# pcb_schematic.net
KiCad netlist of a schematic drawn in EAGLE
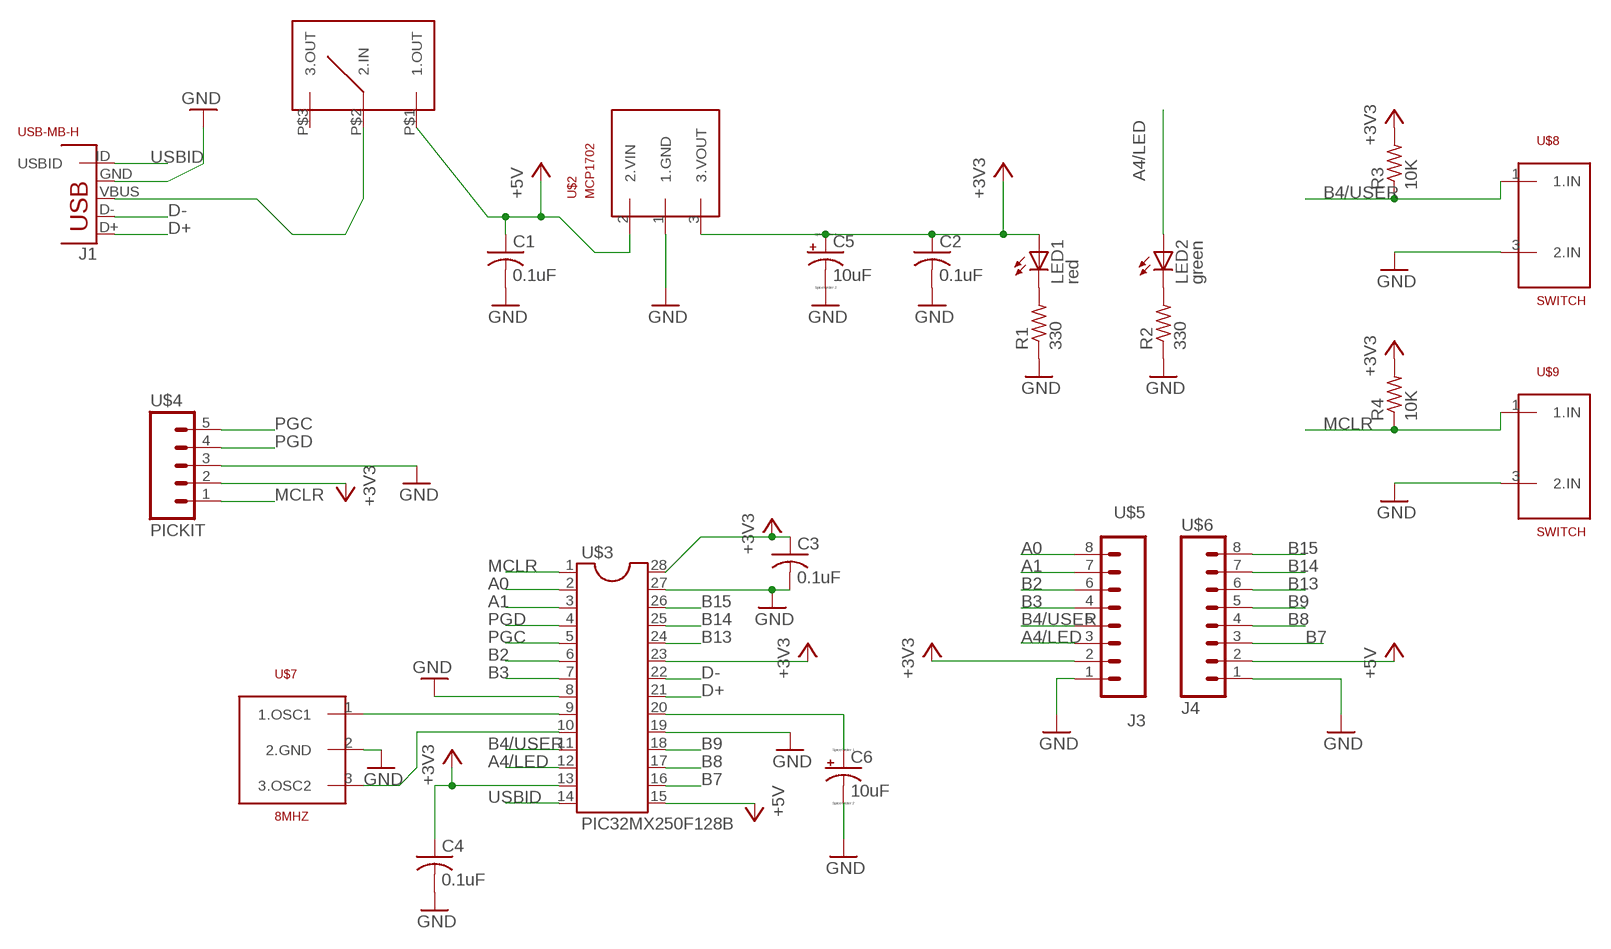
[diagram p0: schematic, sheet 1]

(export (version "E")
  (design (tool "Eeschema 10.0.6"))
  (components
    (comp (ref "C1")
      (value "0.1uF")
      (footprint "eagle-import:C025-025X050")
      (libsource (lib "eagle-import") (part "C-US025-025X050"))
    )
    (comp (ref "C2")
      (value "0.1uF")
      (footprint "eagle-import:C025-025X050")
      (libsource (lib "eagle-import") (part "C-US025-025X050"))
    )
    (comp (ref "C3")
      (value "0.1uF")
      (footprint "eagle-import:C025-025X050")
      (libsource (lib "eagle-import") (part "C-US025-025X050"))
    )
    (comp (ref "C4")
      (value "0.1uF")
      (footprint "eagle-import:C025-025X050")
      (libsource (lib "eagle-import") (part "C-US025-025X050"))
    )
    (comp (ref "C5")
      (value "10uF")
      (footprint "eagle-import:B45181A")
      (libsource (lib "eagle-import") (part "CPOL-USB45181A"))
    )
    (comp (ref "C6")
      (value "10uF")
      (footprint "eagle-import:B45181A")
      (libsource (lib "eagle-import") (part "CPOL-USB45181A"))
    )
    (comp (ref "J1")
      (value "USB-MB-H")
      (footprint "eagle-import:USB-MB-H")
      (libsource (lib "eagle-import") (part "USB-MB-H"))
    )
    (comp (ref "LED1")
      (value "red")
      (footprint "eagle-import:LED3MM")
      (libsource (lib "eagle-import") (part "LED3MM"))
    )
    (comp (ref "LED2")
      (value "green")
      (footprint "eagle-import:LED3MM")
      (libsource (lib "eagle-import") (part "LED3MM"))
    )
    (comp (ref "R1")
      (value "330")
      (footprint "eagle-import:0204_7")
      (libsource (lib "eagle-import") (part "R-US_0204/7"))
    )
    (comp (ref "R2")
      (value "330")
      (footprint "eagle-import:0204_7")
      (libsource (lib "eagle-import") (part "R-US_0204/7"))
    )
    (comp (ref "R3")
      (value "10K")
      (footprint "eagle-import:0204_7")
      (libsource (lib "eagle-import") (part "R-US_0204/7"))
    )
    (comp (ref "R4")
      (value "10K")
      (footprint "eagle-import:0204_7")
      (libsource (lib "eagle-import") (part "R-US_0204/7"))
    )
    (comp (ref "U$1")
      (value "SLIDE_SWITCH")
      (footprint "eagle-import:SLIDE_SWITCH")
      (libsource (lib "eagle-import") (part "SLIDE_SWITCH"))
    )
    (comp (ref "U$2")
      (value "MCP1702")
      (footprint "eagle-import:TO92")
      (libsource (lib "eagle-import") (part "MCP1702"))
    )
    (comp (ref "U$3")
      (value "PIC32MX250F128B")
      (footprint "eagle-import:PIC32MX250F128B")
      (libsource (lib "eagle-import") (part "PIC32MX250F128B"))
    )
    (comp (ref "U$4")
      (value "PICKIT")
      (footprint "eagle-import:PICKIT")
      (libsource (lib "eagle-import") (part "PICKIT"))
    )
    (comp (ref "U$5") (value "J3") (footprint "eagle-import:J3") (libsource (lib "eagle-import") (part "J3")))
    (comp (ref "U$6") (value "J4") (footprint "eagle-import:J4") (libsource (lib "eagle-import") (part "J4")))
    (comp (ref "U$7")
      (value "8MHZ")
      (footprint "eagle-import:8MHZ")
      (libsource (lib "eagle-import") (part "8MHZ"))
    )
    (comp (ref "U$8")
      (value "SWITCH")
      (footprint "eagle-import:SWITCH")
      (libsource (lib "eagle-import") (part "SWITCH"))
    )
    (comp (ref "U$9")
      (value "SWITCH")
      (footprint "eagle-import:SWITCH")
      (libsource (lib "eagle-import") (part "SWITCH"))
    )
  )
  (nets
    (net (code "1") (name "+3V3") (class "Default")
      (node (ref "C2") (pin "1") (pinfunction "1_1") (pintype "passive"))
      (node (ref "C3") (pin "1") (pinfunction "1_1") (pintype "passive"))
      (node (ref "C4") (pin "1") (pinfunction "1_1") (pintype "passive"))
      (node (ref "C5") (pin "+") (pinfunction "+_+") (pintype "passive"))
      (node (ref "LED1") (pin "A") (pinfunction "A_A") (pintype "passive"))
      (node (ref "R3") (pin "2") (pinfunction "2_2") (pintype "passive"))
      (node (ref "R4") (pin "2") (pinfunction "2_2") (pintype "passive"))
      (node (ref "U$2") (pin "3") (pinfunction "3.VOUT_3") (pintype "bidirectional"))
      (node (ref "U$3") (pin "13") (pinfunction "13.VDD_13") (pintype "passive"))
      (node (ref "U$3") (pin "23") (pinfunction "23.VUSB3V3_23") (pintype "passive"))
      (node (ref "U$3") (pin "28") (pinfunction "28.AVDD_28") (pintype "passive"))
      (node (ref "U$4") (pin "2") (pinfunction "2.3V3_2") (pintype "passive"))
      (node (ref "U$5") (pin "2") (pinfunction "2.3V3_2") (pintype "passive"))
    )
    (net (code "2") (name "+5V") (class "Default")
      (node (ref "C1") (pin "1") (pinfunction "1_1") (pintype "passive"))
      (node (ref "U$1") (pin "P$1") (pinfunction "1.OUT_P$1") (pintype "bidirectional"))
      (node (ref "U$2") (pin "2") (pinfunction "2.VIN_2") (pintype "bidirectional"))
      (node (ref "U$3") (pin "15") (pinfunction "15.VBUS_15") (pintype "passive"))
      (node (ref "U$6") (pin "2") (pinfunction "2.5V_2") (pintype "passive"))
    )
    (net (code "3") (name "/A0") (class "Default")
      (node (ref "U$3") (pin "2") (pinfunction "2.A0_2") (pintype "passive"))
      (node (ref "U$5") (pin "8") (pinfunction "8.A0_8") (pintype "passive"))
    )
    (net (code "4") (name "/A1") (class "Default")
      (node (ref "U$3") (pin "3") (pinfunction "3.A1_3") (pintype "passive"))
      (node (ref "U$5") (pin "7") (pinfunction "7.A1_7") (pintype "passive"))
    )
    (net (code "5") (name "/A4{slash}LED") (class "Default")
      (node (ref "LED2") (pin "A") (pinfunction "A_A") (pintype "passive"))
      (node (ref "U$3") (pin "12") (pinfunction "12.A4/LED_12") (pintype "passive"))
      (node (ref "U$5") (pin "3") (pinfunction "3.A4/LED_3") (pintype "passive"))
    )
    (net (code "6") (name "/B2") (class "Default")
      (node (ref "U$3") (pin "6") (pinfunction "6.B2_6") (pintype "passive"))
      (node (ref "U$5") (pin "6") (pinfunction "5.B3_6") (pintype "passive"))
    )
    (net (code "7") (name "/B3") (class "Default")
      (node (ref "U$3") (pin "7") (pinfunction "7.B3_7") (pintype "passive"))
      (node (ref "U$5") (pin "4") (pinfunction "4.B4/USER_4") (pintype "passive"))
    )
    (net (code "8") (name "/B4{slash}USER") (class "Default")
      (node (ref "R3") (pin "1") (pinfunction "1_1") (pintype "passive"))
      (node (ref "U$3") (pin "11") (pinfunction "11.B4/USER_11") (pintype "passive"))
      (node (ref "U$5") (pin "5") (pinfunction "5_5") (pintype "passive"))
      (node (ref "U$8") (pin "1") (pinfunction "1.IN_1") (pintype "bidirectional"))
    )
    (net (code "9") (name "/B7") (class "Default")
      (node (ref "U$3") (pin "16") (pinfunction "16.B7_16") (pintype "passive"))
      (node (ref "U$6") (pin "3") (pinfunction "3.B7_3") (pintype "passive"))
    )
    (net (code "10") (name "/B8") (class "Default")
      (node (ref "U$3") (pin "17") (pinfunction "17.B8_17") (pintype "passive"))
      (node (ref "U$6") (pin "4") (pinfunction "4.B8_4") (pintype "passive"))
    )
    (net (code "11") (name "/B9") (class "Default")
      (node (ref "U$3") (pin "18") (pinfunction "18.B9_18") (pintype "passive"))
      (node (ref "U$6") (pin "5") (pinfunction "5.B9_5") (pintype "passive"))
    )
    (net (code "12") (name "/B13") (class "Default")
      (node (ref "U$3") (pin "24") (pinfunction "24.B13_24") (pintype "passive"))
      (node (ref "U$6") (pin "6") (pinfunction "6.B13_6") (pintype "passive"))
    )
    (net (code "13") (name "/B14") (class "Default")
      (node (ref "U$3") (pin "25") (pinfunction "25.B14_25") (pintype "passive"))
      (node (ref "U$6") (pin "7") (pinfunction "7.B14_7") (pintype "passive"))
    )
    (net (code "14") (name "/B15") (class "Default")
      (node (ref "U$3") (pin "26") (pinfunction "26.B15_26") (pintype "passive"))
      (node (ref "U$6") (pin "8") (pinfunction "8.B15_8") (pintype "passive"))
    )
    (net (code "15") (name "/D+") (class "Default")
      (node (ref "J1") (pin "D+") (pinfunction "D+_D+") (pintype "bidirectional"))
      (node (ref "U$3") (pin "21") (pinfunction "21.D+/B10_21") (pintype "passive"))
    )
    (net (code "16") (name "/D-") (class "Default")
      (node (ref "J1") (pin "D-") (pinfunction "D-_D-") (pintype "bidirectional"))
      (node (ref "U$3") (pin "22") (pinfunction "22.D-/B11_22") (pintype "passive"))
    )
    (net (code "17") (name "/MCLR") (class "Default")
      (node (ref "R4") (pin "1") (pinfunction "1_1") (pintype "passive"))
      (node (ref "U$3") (pin "1") (pinfunction "1.MCLR_1") (pintype "passive"))
      (node (ref "U$4") (pin "1") (pinfunction "1.MCLR_1") (pintype "passive"))
      (node (ref "U$9") (pin "1") (pinfunction "1.IN_1") (pintype "bidirectional"))
    )
    (net (code "18") (name "/PGC") (class "Default")
      (node (ref "U$3") (pin "5") (pinfunction "5.PGC_5") (pintype "passive"))
      (node (ref "U$4") (pin "5") (pinfunction "5.PGC_5") (pintype "passive"))
    )
    (net (code "19") (name "/PGD") (class "Default")
      (node (ref "U$3") (pin "4") (pinfunction "4.PGD_4") (pintype "passive"))
      (node (ref "U$4") (pin "4") (pinfunction "4.PGD_4") (pintype "passive"))
    )
    (net (code "20") (name "/USBID") (class "Default")
      (node (ref "J1") (pin "ID") (pinfunction "USBID_ID") (pintype "bidirectional"))
      (node (ref "U$3") (pin "14") (pinfunction "14.USBID/B5_14") (pintype "passive"))
    )
    (net (code "21") (name "GND") (class "Default")
      (node (ref "C1") (pin "2") (pinfunction "2_2") (pintype "passive"))
      (node (ref "C2") (pin "2") (pinfunction "2_2") (pintype "passive"))
      (node (ref "C3") (pin "2") (pinfunction "2_2") (pintype "passive"))
      (node (ref "C4") (pin "2") (pinfunction "2_2") (pintype "passive"))
      (node (ref "C5") (pin "-") (pinfunction "-_-") (pintype "passive"))
      (node (ref "C6") (pin "-") (pinfunction "-_-") (pintype "passive"))
      (node (ref "J1") (pin "GND") (pinfunction "GND_GND") (pintype "bidirectional"))
      (node (ref "R1") (pin "1") (pinfunction "1_1") (pintype "passive"))
      (node (ref "R2") (pin "1") (pinfunction "1_1") (pintype "passive"))
      (node (ref "U$2") (pin "1") (pinfunction "1.GND_1") (pintype "bidirectional"))
      (node (ref "U$3") (pin "19") (pinfunction "19.VSS_19") (pintype "passive"))
      (node (ref "U$3") (pin "27") (pinfunction "27.AVSS_27") (pintype "passive"))
      (node (ref "U$3") (pin "8") (pinfunction "8.GND_8") (pintype "passive"))
      (node (ref "U$4") (pin "3") (pinfunction "3.GND_3") (pintype "passive"))
      (node (ref "U$5") (pin "1") (pinfunction "1.GND_1") (pintype "passive"))
      (node (ref "U$6") (pin "1") (pinfunction "1.GND_1") (pintype "passive"))
      (node (ref "U$7") (pin "2") (pinfunction "2.GND_2") (pintype "bidirectional"))
      (node (ref "U$8") (pin "3") (pinfunction "2.IN_3") (pintype "bidirectional"))
      (node (ref "U$9") (pin "3") (pinfunction "2.IN_3") (pintype "bidirectional"))
    )
    (net (code "22") (name "Net-(LED1-C)") (class "Default")
      (node (ref "LED1") (pin "K") (pinfunction "C_K") (pintype "passive"))
      (node (ref "R1") (pin "2") (pinfunction "2_2") (pintype "passive"))
    )
    (net (code "23") (name "Net-(LED2-C)") (class "Default")
      (node (ref "LED2") (pin "K") (pinfunction "C_K") (pintype "passive"))
      (node (ref "R2") (pin "2") (pinfunction "2_2") (pintype "passive"))
    )
    (net (code "24") (name "Net-(U$1-2.IN)") (class "Default")
      (node (ref "J1") (pin "VBUS") (pinfunction "VBUS_VBUS") (pintype "bidirectional"))
      (node (ref "U$1") (pin "P$2") (pinfunction "2.IN_P$2") (pintype "bidirectional"))
    )
    (net (code "25") (name "Net-(U$3-9.OSC1)") (class "Default")
      (node (ref "U$3") (pin "9") (pinfunction "9.OSC1_9") (pintype "passive"))
      (node (ref "U$7") (pin "1") (pinfunction "1.OSC1_1") (pintype "bidirectional"))
    )
    (net (code "26") (name "Net-(U$3-10.OSC2)") (class "Default")
      (node (ref "U$3") (pin "10") (pinfunction "10.OSC2_10") (pintype "passive"))
      (node (ref "U$7") (pin "3") (pinfunction "3.OSC2_3") (pintype "bidirectional"))
    )
    (net (code "27") (name "Net-(U$3-20.VCAP)") (class "Default")
      (node (ref "C6") (pin "+") (pinfunction "+_+") (pintype "passive"))
      (node (ref "U$3") (pin "20") (pinfunction "20.VCAP_20") (pintype "passive"))
    )
    (net (code "28") (name "unconnected-(U$1-3.OUT-PadP$3)") (class "Default")
      (node (ref "U$1") (pin "P$3") (pinfunction "3.OUT_P$3") (pintype "bidirectional"))
    )
  )
)
